# Start-stop_interrupt.net
KiCad netlist of a schematic drawn in EAGLE
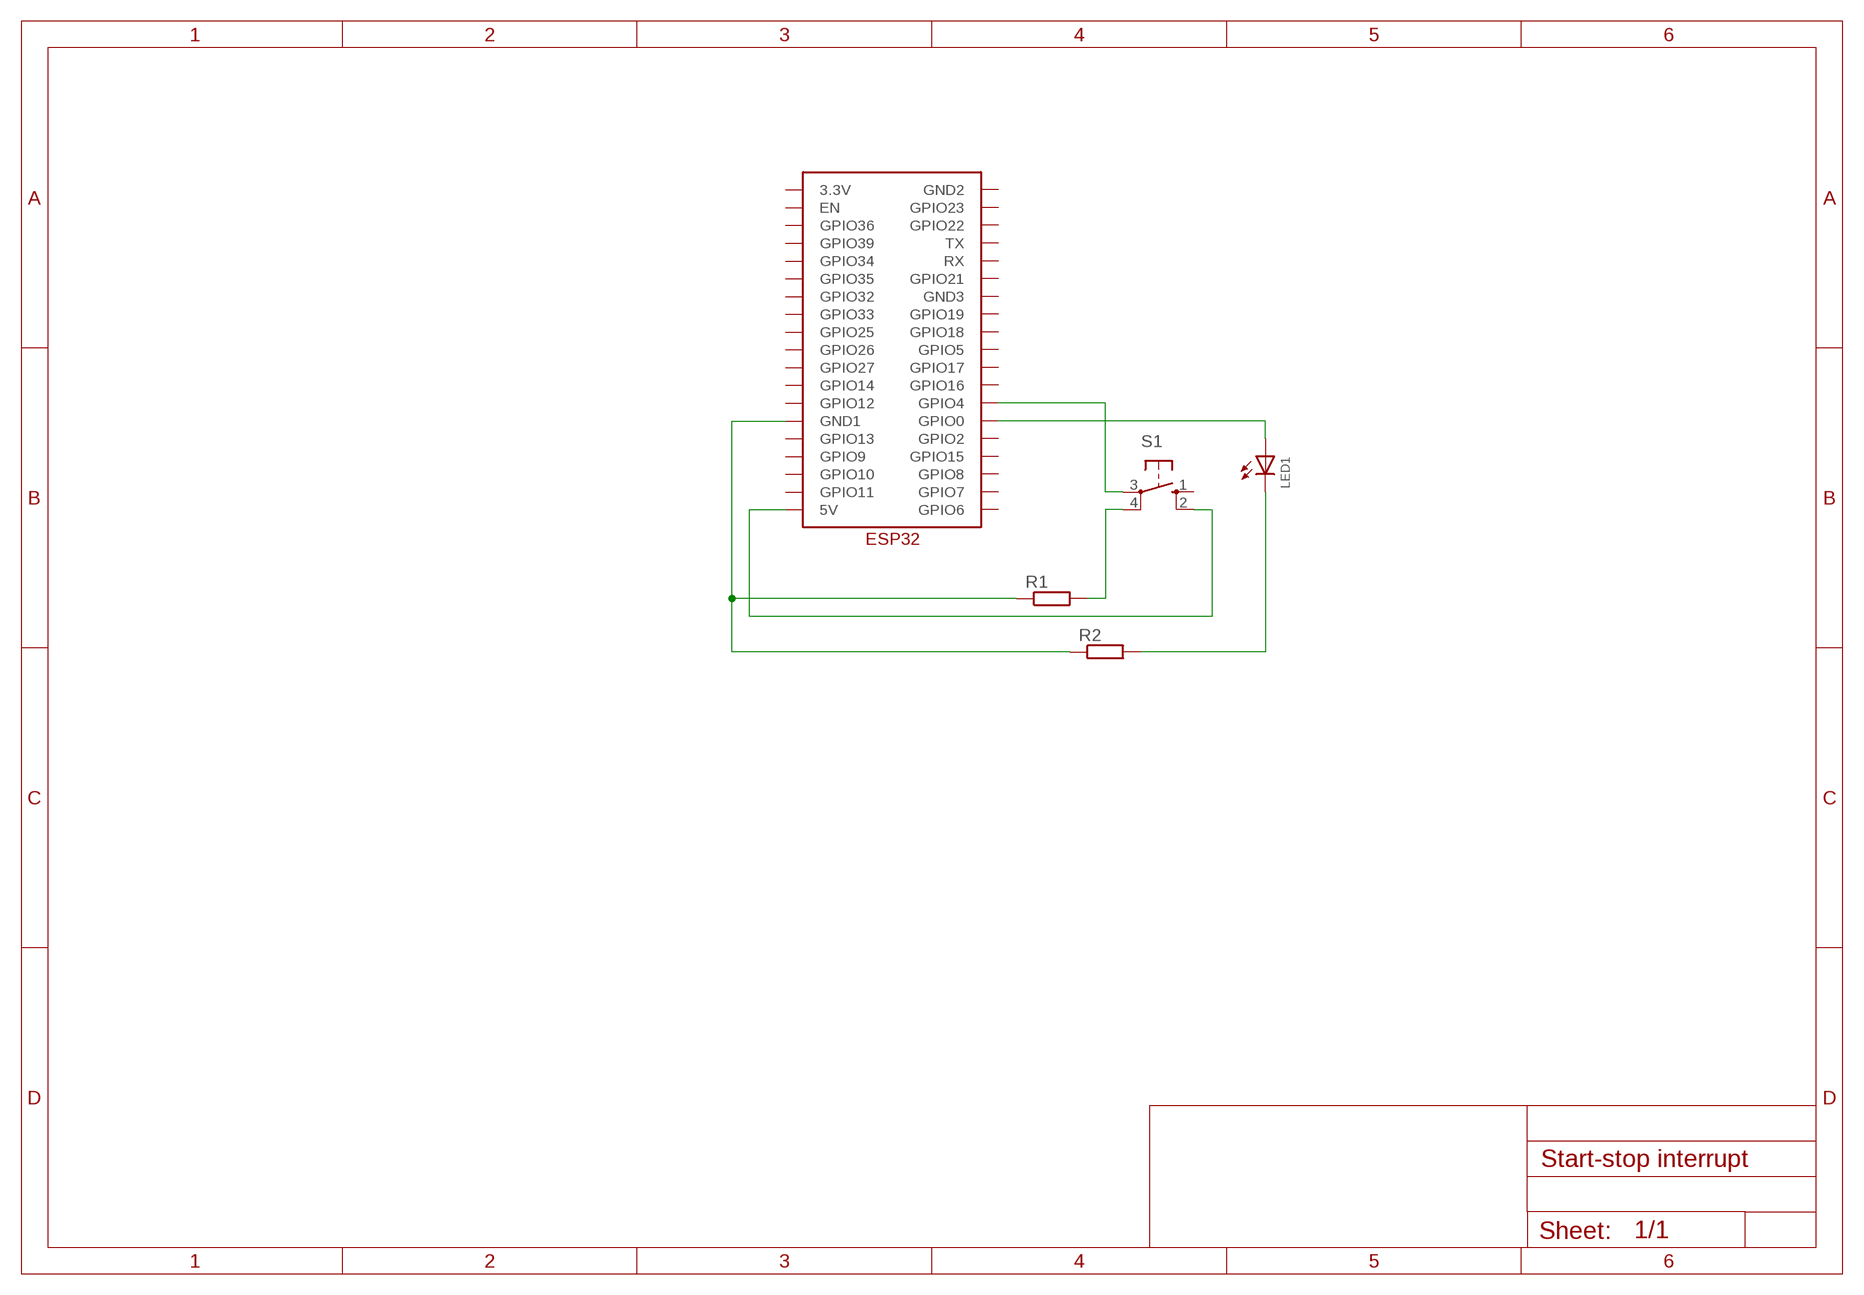
[diagram p0: schematic, sheet 1]

(export (version "E")
  (design (tool "Eeschema 10.0.6"))
  (components
    (comp (ref "LED1")
      (value "LED-3MM-GREEN")
      (footprint "eagle-import:LED3MM")
      (fields (field (name "MF") "VISHAY SEMICONDUCTOR"))
      (libsource (lib "eagle-import") (part "LED-3MM-GREEN"))
    )
    (comp (ref "R1")
      (value "R-EU_0204/7")
      (footprint "eagle-import:0204_7")
      (libsource (lib "eagle-import") (part "R-EU_0204/7"))
    )
    (comp (ref "R2")
      (value "R-EU_0204/7")
      (footprint "eagle-import:0204_7")
      (libsource (lib "eagle-import") (part "R-EU_0204/7"))
    )
    (comp (ref "S1")
      (value "10-XX")
      (footprint "eagle-import:B3F-10XX")
      (fields (field (name "MPN") "B3F-1000"))
      (libsource (lib "eagle-import") (part "10-XX"))
    )
    (comp (ref "U$1")
      (value "ESP32_GRBL")
      (footprint "eagle-import:ESP32_GRBL")
      (libsource (lib "eagle-import") (part "ESP32_GRBL"))
    )
  )
  (nets
    (net (code "1") (name "Net-(LED1-C)") (class "Default")
      (node (ref "LED1") (pin "K") (pinfunction "C_K") (pintype "passive"))
      (node (ref "R2") (pin "2") (pinfunction "2_2") (pintype "passive"))
    )
    (net (code "2") (name "Net-(LED1-PadA)") (class "Default")
      (node (ref "LED1") (pin "A") (pinfunction "A_A") (pintype "passive"))
      (node (ref "U$1") (pin "GPIO0") (pinfunction "GPIO0_GPIO0") (pintype "bidirectional"))
    )
    (net (code "3") (name "Net-(R1-Pad1)") (class "Default")
      (node (ref "R1") (pin "1") (pinfunction "1_1") (pintype "passive"))
      (node (ref "R2") (pin "1") (pinfunction "1_1") (pintype "passive"))
      (node (ref "U$1") (pin "GND1") (pinfunction "GND1_GND1") (pintype "bidirectional"))
    )
    (net (code "4") (name "Net-(S1-P)") (class "Default")
      (node (ref "S1") (pin "3") (pinfunction "P_3") (pintype "passive"))
      (node (ref "U$1") (pin "GPIO4") (pinfunction "GPIO4_GPIO4") (pintype "bidirectional"))
    )
    (net (code "5") (name "Net-(S1-P1)") (class "Default")
      (node (ref "R1") (pin "2") (pinfunction "2_2") (pintype "passive"))
      (node (ref "S1") (pin "4") (pinfunction "P1_4") (pintype "passive"))
    )
    (net (code "6") (name "Net-(S1-S1)") (class "Default")
      (node (ref "S1") (pin "2") (pinfunction "S1_2") (pintype "passive"))
      (node (ref "U$1") (pin "5V") (pinfunction "5V_5V") (pintype "bidirectional"))
    )
    (net (code "7") (name "unconnected-(S1-S-Pad1)") (class "Default")
      (node (ref "S1") (pin "1") (pinfunction "S_1") (pintype "passive"))
    )
    (net (code "8") (name "unconnected-(U$1-Pad3.3V)") (class "Default")
      (node (ref "U$1") (pin "3.3V") (pinfunction "3.3V_3.3V") (pintype "bidirectional"))
    )
    (net (code "9") (name "unconnected-(U$1-PadEN)") (class "Default")
      (node (ref "U$1") (pin "EN") (pinfunction "EN_EN") (pintype "bidirectional"))
    )
    (net (code "10") (name "unconnected-(U$1-PadGND2)") (class "Default")
      (node (ref "U$1") (pin "GND2") (pinfunction "GND2_GND2") (pintype "bidirectional"))
    )
    (net (code "11") (name "unconnected-(U$1-PadGND3)") (class "Default")
      (node (ref "U$1") (pin "GND3") (pinfunction "GND3_GND3") (pintype "bidirectional"))
    )
    (net (code "12") (name "unconnected-(U$1-PadGPIO2)") (class "Default")
      (node (ref "U$1") (pin "GPIO2") (pinfunction "GPIO2_GPIO2") (pintype "bidirectional"))
    )
    (net (code "13") (name "unconnected-(U$1-PadGPIO5)") (class "Default")
      (node (ref "U$1") (pin "GPIO5") (pinfunction "GPIO5_GPIO5") (pintype "bidirectional"))
    )
    (net (code "14") (name "unconnected-(U$1-PadGPIO6)") (class "Default")
      (node (ref "U$1") (pin "GPIO6") (pinfunction "GPIO6_GPIO6") (pintype "bidirectional"))
    )
    (net (code "15") (name "unconnected-(U$1-PadGPIO7)") (class "Default")
      (node (ref "U$1") (pin "GPIO7") (pinfunction "GPIO7_GPIO7") (pintype "bidirectional"))
    )
    (net (code "16") (name "unconnected-(U$1-PadGPIO8)") (class "Default")
      (node (ref "U$1") (pin "GPIO8") (pinfunction "GPIO8_GPIO8") (pintype "bidirectional"))
    )
    (net (code "17") (name "unconnected-(U$1-PadGPIO9)") (class "Default")
      (node (ref "U$1") (pin "GPIO9") (pinfunction "GPIO9_GPIO9") (pintype "bidirectional"))
    )
    (net (code "18") (name "unconnected-(U$1-PadGPIO10)") (class "Default")
      (node (ref "U$1") (pin "GPIO10") (pinfunction "GPIO10_GPIO10") (pintype "bidirectional"))
    )
    (net (code "19") (name "unconnected-(U$1-PadGPIO11)") (class "Default")
      (node (ref "U$1") (pin "GPIO11") (pinfunction "GPIO11_GPIO11") (pintype "bidirectional"))
    )
    (net (code "20") (name "unconnected-(U$1-PadGPIO12)") (class "Default")
      (node (ref "U$1") (pin "GPIO12") (pinfunction "GPIO12_GPIO12") (pintype "bidirectional"))
    )
    (net (code "21") (name "unconnected-(U$1-PadGPIO13)") (class "Default")
      (node (ref "U$1") (pin "GPIO13") (pinfunction "GPIO13_GPIO13") (pintype "bidirectional"))
    )
    (net (code "22") (name "unconnected-(U$1-PadGPIO14)") (class "Default")
      (node (ref "U$1") (pin "GPIO14") (pinfunction "GPIO14_GPIO14") (pintype "bidirectional"))
    )
    (net (code "23") (name "unconnected-(U$1-PadGPIO15)") (class "Default")
      (node (ref "U$1") (pin "GPIO15") (pinfunction "GPIO15_GPIO15") (pintype "bidirectional"))
    )
    (net (code "24") (name "unconnected-(U$1-PadGPIO16)") (class "Default")
      (node (ref "U$1") (pin "GPIO16") (pinfunction "GPIO16_GPIO16") (pintype "bidirectional"))
    )
    (net (code "25") (name "unconnected-(U$1-PadGPIO17)") (class "Default")
      (node (ref "U$1") (pin "GPIO17") (pinfunction "GPIO17_GPIO17") (pintype "bidirectional"))
    )
    (net (code "26") (name "unconnected-(U$1-PadGPIO18)") (class "Default")
      (node (ref "U$1") (pin "GPIO18") (pinfunction "GPIO18_GPIO18") (pintype "bidirectional"))
    )
    (net (code "27") (name "unconnected-(U$1-PadGPIO19)") (class "Default")
      (node (ref "U$1") (pin "GPIO19") (pinfunction "GPIO19_GPIO19") (pintype "bidirectional"))
    )
    (net (code "28") (name "unconnected-(U$1-PadGPIO21)") (class "Default")
      (node (ref "U$1") (pin "GPIO21") (pinfunction "GPIO21_GPIO21") (pintype "bidirectional"))
    )
    (net (code "29") (name "unconnected-(U$1-PadGPIO22)") (class "Default")
      (node (ref "U$1") (pin "GPIO22") (pinfunction "GPIO22_GPIO22") (pintype "bidirectional"))
    )
    (net (code "30") (name "unconnected-(U$1-PadGPIO23)") (class "Default")
      (node (ref "U$1") (pin "GPIO23") (pinfunction "GPIO23_GPIO23") (pintype "bidirectional"))
    )
    (net (code "31") (name "unconnected-(U$1-PadGPIO25)") (class "Default")
      (node (ref "U$1") (pin "GPIO25") (pinfunction "GPIO25_GPIO25") (pintype "bidirectional"))
    )
    (net (code "32") (name "unconnected-(U$1-PadGPIO26)") (class "Default")
      (node (ref "U$1") (pin "GPIO26") (pinfunction "GPIO26_GPIO26") (pintype "bidirectional"))
    )
    (net (code "33") (name "unconnected-(U$1-PadGPIO27)") (class "Default")
      (node (ref "U$1") (pin "GPIO27") (pinfunction "GPIO27_GPIO27") (pintype "bidirectional"))
    )
    (net (code "34") (name "unconnected-(U$1-PadGPIO32)") (class "Default")
      (node (ref "U$1") (pin "GPIO32") (pinfunction "GPIO32_GPIO32") (pintype "bidirectional"))
    )
    (net (code "35") (name "unconnected-(U$1-PadGPIO33)") (class "Default")
      (node (ref "U$1") (pin "GPIO33") (pinfunction "GPIO33_GPIO33") (pintype "bidirectional"))
    )
    (net (code "36") (name "unconnected-(U$1-PadGPIO34)") (class "Default")
      (node (ref "U$1") (pin "GPIO34") (pinfunction "GPIO34_GPIO34") (pintype "bidirectional"))
    )
    (net (code "37") (name "unconnected-(U$1-PadGPIO35)") (class "Default")
      (node (ref "U$1") (pin "GPIO35") (pinfunction "GPIO35_GPIO35") (pintype "bidirectional"))
    )
    (net (code "38") (name "unconnected-(U$1-PadGPIO36)") (class "Default")
      (node (ref "U$1") (pin "GPIO36") (pinfunction "GPIO36_GPIO36") (pintype "bidirectional"))
    )
    (net (code "39") (name "unconnected-(U$1-PadGPIO39)") (class "Default")
      (node (ref "U$1") (pin "GPIO39") (pinfunction "GPIO39_GPIO39") (pintype "bidirectional"))
    )
    (net (code "40") (name "unconnected-(U$1-PadRX)") (class "Default")
      (node (ref "U$1") (pin "RX") (pinfunction "RX_RX") (pintype "bidirectional"))
    )
    (net (code "41") (name "unconnected-(U$1-PadTX)") (class "Default")
      (node (ref "U$1") (pin "TX") (pinfunction "TX_TX") (pintype "bidirectional"))
    )
  )
)
